# Sheet1.net
KiCad netlist of a schematic drawn in Altium Designer
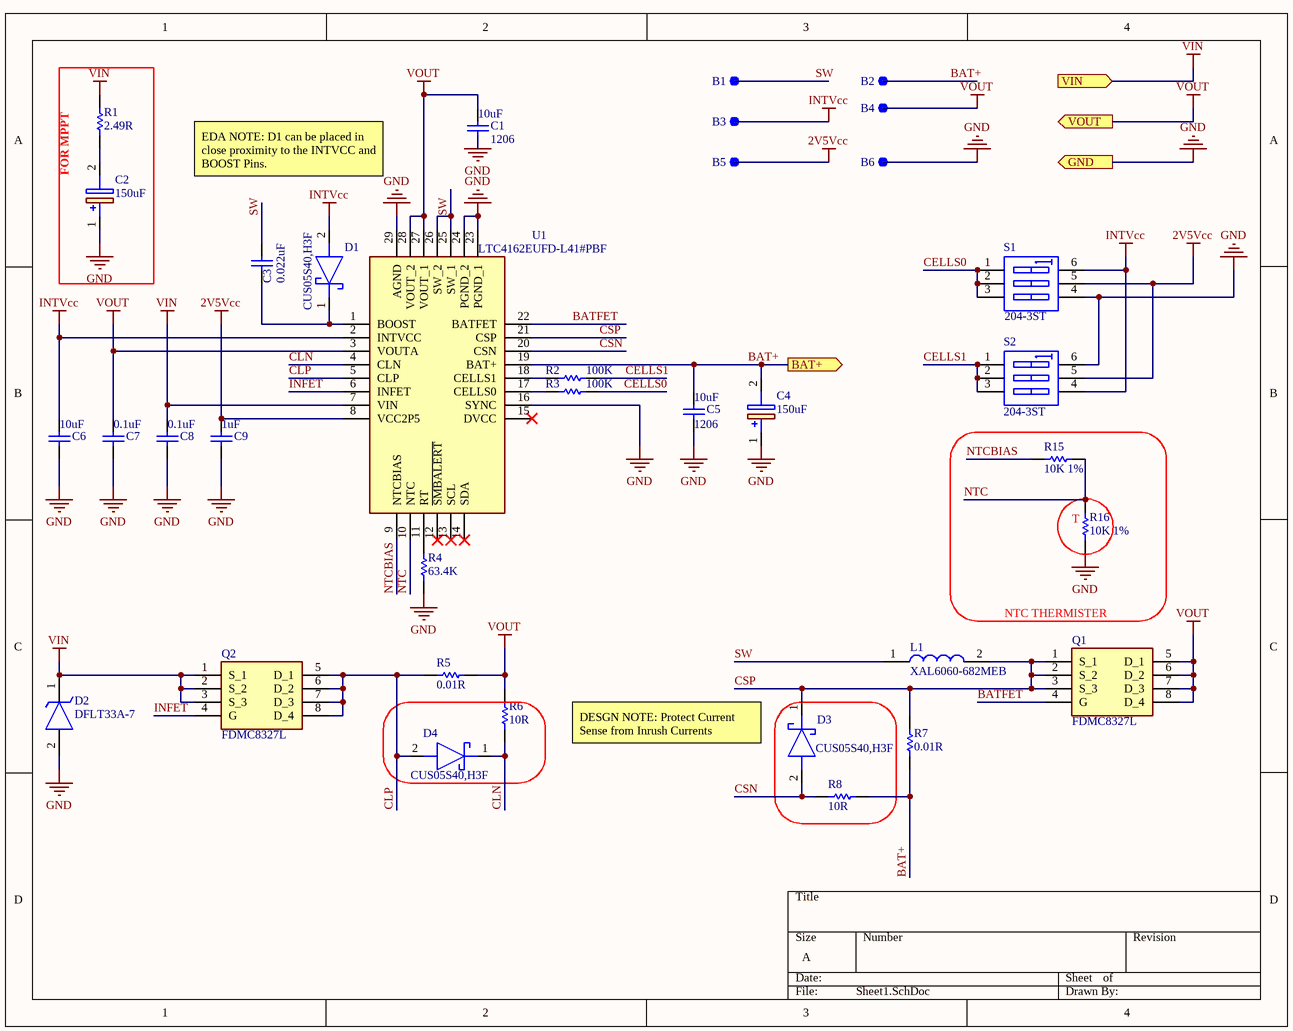
[diagram p0: Sheet1.SchDoc]

(export (version "E")
  (design (tool "Eeschema 10.0.6"))
  (components
    (comp (ref "B1")
      (value "~")
      (footprint "Pads:TPS127")
      (description "Through Hole Pad")
      (libsource (lib "Pads") (part "Single SMD Pad (Round)"))
    )
    (comp (ref "B2")
      (value "~")
      (footprint "Pads:TPS127")
      (description "Through Hole Pad")
      (libsource (lib "Pads") (part "Single SMD Pad (Round)"))
    )
    (comp (ref "B3")
      (value "~")
      (footprint "Pads:TPS127")
      (description "Through Hole Pad")
      (libsource (lib "Pads") (part "Single SMD Pad (Round)"))
    )
    (comp (ref "B4")
      (value "~")
      (footprint "Pads:TPS127")
      (description "Through Hole Pad")
      (libsource (lib "Pads") (part "Single SMD Pad (Round)"))
    )
    (comp (ref "B5")
      (value "~")
      (footprint "Pads:TPS127")
      (description "Through Hole Pad")
      (libsource (lib "Pads") (part "Single SMD Pad (Round)"))
    )
    (comp (ref "B6")
      (value "~")
      (footprint "Pads:TPS127")
      (description "Through Hole Pad")
      (libsource (lib "Pads") (part "Single SMD Pad (Round)"))
    )
    (comp (ref "C1")
      (value "1206")
      (footprint "CAPC3216X152N")
      (description "Capacitor")
      (fields (field (name "ALTIUM_VALUE") "10uF") (field (name "PUBLISHER") "Altium Limited"))
      (libsource (lib "Miscellaneous Devices") (part "Cap"))
    )
    (comp (ref "C2")
      (value "150uF")
      (footprint "SamacSys:CAPAE1030X1050N")
      (description "Capacitor Polarised")
      (fields (field (name "MANUFACTURER_PART_NUMBER") "EEEFK1H151P"))
      (libsource (lib "*") (part "EEEFK1H151P"))
    )
    (comp (ref "C3")
      (value "0.022uF")
      (footprint "Capacitors SMD:CAPC1608X80N")
      (description "Capacitor")
      (fields (field (name "Comment") "Cap") (field (name "PUBLISHER") "Altium Limited"))
      (libsource (lib "Miscellaneous Devices") (part "Cap"))
    )
    (comp (ref "C4")
      (value "150uF")
      (footprint "SamacSys:CAPAE1030X1050N")
      (description "Capacitor Polarised")
      (fields (field (name "MANUFACTURER_PART_NUMBER") "EEEFK1H151P"))
      (libsource (lib "*") (part "EEEFK1H151P"))
    )
    (comp (ref "C5")
      (value "1206")
      (footprint "CAPC3216X152N")
      (description "Capacitor")
      (fields (field (name "ALTIUM_VALUE") "10uF") (field (name "PUBLISHER") "Altium Limited"))
      (libsource (lib "Miscellaneous Devices") (part "Cap"))
    )
    (comp (ref "C6")
      (value "10uF")
      (footprint "Capacitors SMD:CAPC1608X80N")
      (description "Capacitor")
      (fields (field (name "Comment") "Cap") (field (name "PUBLISHER") "Altium Limited"))
      (libsource (lib "Miscellaneous Devices") (part "Cap"))
    )
    (comp (ref "C7")
      (value "0.1uF")
      (footprint "Capacitors SMD:CAPC1608X80N")
      (description "Capacitor")
      (fields (field (name "Comment") "Cap") (field (name "PUBLISHER") "Altium Limited"))
      (libsource (lib "Miscellaneous Devices") (part "Cap"))
    )
    (comp (ref "C8")
      (value "0.1uF")
      (footprint "Capacitors SMD:CAPC1608X80N")
      (description "Capacitor")
      (fields (field (name "Comment") "Cap") (field (name "PUBLISHER") "Altium Limited"))
      (libsource (lib "Miscellaneous Devices") (part "Cap"))
    )
    (comp (ref "C9")
      (value "1uF")
      (footprint "Capacitors SMD:CAPC1608X80N")
      (description "Capacitor")
      (fields (field (name "Comment") "Cap") (field (name "PUBLISHER") "Altium Limited"))
      (libsource (lib "Miscellaneous Devices") (part "Cap"))
    )
    (comp (ref "D1")
      (value "CUS05S40,H3F")
      (footprint "SamacSys:1SS357TPH3F")
      (description "Schottky Diode")
      (fields (field (name "MOUSER PART NUMBER") "757-CUS05S40H3F"))
      (libsource (lib "*") (part "CUS05S40,H3F"))
    )
    (comp (ref "D2")
      (value "DFLT33A-7")
      (footprint "SamacSys:POWERDI123_1")
      (description "TVS Diode (Uni-directional)")
      (fields
        (field (name "MANUFACTURER_PART_NUMBER") "DFLT27A-7")
        (field (name "MOUSER PART NUMBER") "621-DFLT27A-7")
      )
      (libsource (lib "*") (part "DFLT27A-7"))
    )
    (comp (ref "D3")
      (value "CUS05S40,H3F")
      (footprint "SamacSys:1SS357TPH3F")
      (description "Schottky Diode")
      (fields (field (name "MOUSER PART NUMBER") "757-CUS05S40H3F"))
      (libsource (lib "*") (part "CUS05S40,H3F"))
    )
    (comp (ref "D4")
      (value "CUS05S40,H3F")
      (footprint "SamacSys:1SS357TPH3F")
      (description "Schottky Diode")
      (fields (field (name "MOUSER PART NUMBER") "757-CUS05S40H3F"))
      (libsource (lib "*") (part "CUS05S40,H3F"))
    )
    (comp (ref "L1")
      (value "XAL6060-682MEB")
      (footprint "SamacSys:XAL6060822MEB")
      (description "Inductor")
      (fields (field (name "MOUSER PART NUMBER") "994-XAL6060-682MEB"))
      (libsource (lib "*") (part "XAL6060-682MEB"))
    )
    (comp (ref "Q1")
      (value "FDMC8327L")
      (footprint "SamacSys:FDMC86139P")
      (description "MOSFET (N-Channel)")
      (fields (field (name "MOUSER PART NUMBER") "512-FDMC8327L"))
      (libsource (lib "*") (part "FDMC8327L"))
    )
    (comp (ref "Q2")
      (value "FDMC8327L")
      (footprint "SamacSys:FDMC86139P")
      (description "MOSFET (N-Channel)")
      (fields (field (name "MOUSER PART NUMBER") "512-FDMC8327L"))
      (libsource (lib "*") (part "FDMC8327L"))
    )
    (comp (ref "R1")
      (value "2.49R")
      (footprint "Resistors SMD:RESC3216X60N")
      (description "Semiconductor Resistor")
      (fields (field (name "Comment") "Res Semi") (field (name "PUBLISHER") "Altium Limited"))
      (libsource (lib "Miscellaneous Devices") (part "Res Semi"))
    )
    (comp (ref "R2")
      (value "100K")
      (footprint "RESC1608X55N")
      (description "Semiconductor Resistor")
      (fields (field (name "Comment") "Res Semi") (field (name "PUBLISHER") "Altium Limited"))
      (libsource (lib "Miscellaneous Devices") (part "Res Semi"))
    )
    (comp (ref "R3")
      (value "100K")
      (footprint "RESC1608X55N")
      (description "Semiconductor Resistor")
      (fields (field (name "Comment") "Res Semi") (field (name "PUBLISHER") "Altium Limited"))
      (libsource (lib "Miscellaneous Devices") (part "Res Semi"))
    )
    (comp (ref "R4")
      (value "63.4K")
      (footprint "RESC1608X55N")
      (description "Semiconductor Resistor")
      (fields (field (name "Comment") "Res Semi") (field (name "PUBLISHER") "Altium Limited"))
      (libsource (lib "Miscellaneous Devices") (part "Res Semi"))
    )
    (comp (ref "R5")
      (value "0.01R")
      (footprint "RESC3216X60N")
      (description "Semiconductor Resistor")
      (fields (field (name "Comment") "Res Semi") (field (name "PUBLISHER") "Altium Limited"))
      (libsource (lib "Miscellaneous Devices") (part "Res Semi"))
    )
    (comp (ref "R6")
      (value "10R")
      (footprint "RESC1608X55N")
      (description "Semiconductor Resistor")
      (fields (field (name "Comment") "Res Semi") (field (name "PUBLISHER") "Altium Limited"))
      (libsource (lib "Miscellaneous Devices") (part "Res Semi"))
    )
    (comp (ref "R7")
      (value "0.01R")
      (footprint "RESC3216X60N")
      (description "Semiconductor Resistor")
      (fields (field (name "Comment") "Res Semi") (field (name "PUBLISHER") "Altium Limited"))
      (libsource (lib "Miscellaneous Devices") (part "Res Semi"))
    )
    (comp (ref "R8")
      (value "10R")
      (footprint "RESC1608X55N")
      (description "Semiconductor Resistor")
      (fields (field (name "Comment") "Res Semi") (field (name "PUBLISHER") "Altium Limited"))
      (libsource (lib "Miscellaneous Devices") (part "Res Semi"))
    )
    (comp (ref "R15")
      (value "10K 1%")
      (footprint "RESC1608X55N")
      (description "Semiconductor Resistor")
      (fields (field (name "Comment") "Res Semi") (field (name "PUBLISHER") "Altium Limited"))
      (libsource (lib "Miscellaneous Devices") (part "Res Semi"))
    )
    (comp (ref "R16")
      (value "10K 1%")
      (footprint "RESC1005X40N")
      (description "Semiconductor Resistor")
      (fields (field (name "Comment") "Res Semi") (field (name "PUBLISHER") "Altium Limited"))
      (libsource (lib "Miscellaneous Devices") (part "Res Semi"))
    )
    (comp (ref "S1")
      (value "204-3ST")
      (footprint "204-3ST")
      (description "DIP Switch, 3 Position, SPST")
      (fields (field (name "PUBLISHER") "Altium Limited"))
      (libsource (lib "Miscellaneous Devices") (part "SW DIP-3"))
    )
    (comp (ref "S2")
      (value "204-3ST")
      (footprint "204-3ST")
      (description "DIP Switch, 3 Position, SPST")
      (fields (field (name "PUBLISHER") "Altium Limited"))
      (libsource (lib "Miscellaneous Devices") (part "SW DIP-3"))
    )
    (comp (ref "U1")
      (value "LTC4162EUFD-L41#PBF")
      (footprint "Battery_Charger_LTC4162:LTC4162-L")
      (description "Integrated Circuit")
      (fields (field (name "MOUSER PART NUMBER") "584-4162EUFDL41PB"))
      (libsource (lib "*") (part "LTC4162EUFD-L41#PBF"))
    )
  )
  (nets
    (net (code "1") (name "/BAT+") (class "Default")
      (node (ref "B2") (pin "1") (pinfunction "1_1") (pintype "bidirectional"))
      (node (ref "C4") (pin "2") (pinfunction "-_2") (pintype "passive"))
      (node (ref "C5") (pin "2") (pinfunction "2_2") (pintype "passive"))
      (node (ref "R7") (pin "2") (pinfunction "2_2") (pintype "passive"))
      (node (ref "R8") (pin "1") (pinfunction "1_1") (pintype "passive"))
      (node (ref "U1") (pin "19") (pinfunction "BAT+_19") (pintype "passive"))
    )
    (net (code "2") (name "/BATFET") (class "Default")
      (node (ref "Q1") (pin "4") (pinfunction "G_4") (pintype "passive"))
      (node (ref "U1") (pin "22") (pinfunction "BATFET_22") (pintype "passive"))
    )
    (net (code "3") (name "/CELLS0") (class "Default")
      (node (ref "R3") (pin "2") (pinfunction "2_2") (pintype "passive"))
      (node (ref "S1") (pin "1") (pinfunction "A1_1") (pintype "passive"))
      (node (ref "S1") (pin "2") (pinfunction "A2_2") (pintype "passive"))
      (node (ref "S1") (pin "3") (pinfunction "A3_3") (pintype "passive"))
    )
    (net (code "4") (name "/CELLS1") (class "Default")
      (node (ref "R2") (pin "2") (pinfunction "2_2") (pintype "passive"))
      (node (ref "S2") (pin "1") (pinfunction "A1_1") (pintype "passive"))
      (node (ref "S2") (pin "2") (pinfunction "A2_2") (pintype "passive"))
      (node (ref "S2") (pin "3") (pinfunction "A3_3") (pintype "passive"))
    )
    (net (code "5") (name "/CLN") (class "Default")
      (node (ref "D4") (pin "1") (pinfunction "K_1") (pintype "passive"))
      (node (ref "R6") (pin "1") (pinfunction "1_1") (pintype "passive"))
      (node (ref "U1") (pin "4") (pinfunction "CLN_4") (pintype "passive"))
    )
    (net (code "6") (name "/CLP") (class "Default")
      (node (ref "D4") (pin "2") (pinfunction "A_2") (pintype "passive"))
      (node (ref "Q2") (pin "5") (pinfunction "D_1_5") (pintype "passive"))
      (node (ref "Q2") (pin "6") (pinfunction "D_2_6") (pintype "passive"))
      (node (ref "Q2") (pin "7") (pinfunction "D_3_7") (pintype "passive"))
      (node (ref "Q2") (pin "8") (pinfunction "D_4_8") (pintype "passive"))
      (node (ref "R5") (pin "2") (pinfunction "2_2") (pintype "passive"))
      (node (ref "U1") (pin "5") (pinfunction "CLP_5") (pintype "passive"))
    )
    (net (code "7") (name "/CSN") (class "Default")
      (node (ref "D3") (pin "2") (pinfunction "A_2") (pintype "passive"))
      (node (ref "R8") (pin "2") (pinfunction "2_2") (pintype "passive"))
      (node (ref "U1") (pin "20") (pinfunction "CSN_20") (pintype "passive"))
    )
    (net (code "8") (name "/CSP") (class "Default")
      (node (ref "D3") (pin "1") (pinfunction "K_1") (pintype "passive"))
      (node (ref "L1") (pin "2") (pinfunction "2_2") (pintype "passive"))
      (node (ref "Q1") (pin "1") (pinfunction "S_1_1") (pintype "passive"))
      (node (ref "Q1") (pin "2") (pinfunction "S_2_2") (pintype "passive"))
      (node (ref "Q1") (pin "3") (pinfunction "S_3_3") (pintype "passive"))
      (node (ref "R7") (pin "1") (pinfunction "1_1") (pintype "passive"))
      (node (ref "U1") (pin "21") (pinfunction "CSP_21") (pintype "passive"))
    )
    (net (code "9") (name "/INFET") (class "Default")
      (node (ref "Q2") (pin "4") (pinfunction "G_4") (pintype "passive"))
      (node (ref "U1") (pin "6") (pinfunction "INFET_6") (pintype "passive"))
    )
    (net (code "10") (name "/NTC") (class "Default")
      (node (ref "R15") (pin "1") (pinfunction "1_1") (pintype "passive"))
      (node (ref "R16") (pin "1") (pinfunction "1_1") (pintype "passive"))
      (node (ref "U1") (pin "10") (pinfunction "NTC_10") (pintype "passive"))
    )
    (net (code "11") (name "/NTCBIAS") (class "Default")
      (node (ref "R15") (pin "2") (pinfunction "2_2") (pintype "passive"))
      (node (ref "U1") (pin "9") (pinfunction "NTCBIAS_9") (pintype "passive"))
    )
    (net (code "12") (name "/SW") (class "Default")
      (node (ref "B1") (pin "1") (pinfunction "1_1") (pintype "bidirectional"))
      (node (ref "C3") (pin "1") (pinfunction "1_1") (pintype "passive"))
      (node (ref "L1") (pin "1") (pinfunction "1_1") (pintype "passive"))
      (node (ref "U1") (pin "25") (pinfunction "SW_1_25") (pintype "passive"))
      (node (ref "U1") (pin "26") (pinfunction "SW_2_26") (pintype "passive"))
    )
    (net (code "13") (name "2V5Vcc") (class "Default")
      (node (ref "B5") (pin "1") (pinfunction "1_1") (pintype "bidirectional"))
      (node (ref "C9") (pin "2") (pinfunction "2_2") (pintype "passive"))
      (node (ref "S1") (pin "5") (pinfunction "B2_5") (pintype "passive"))
      (node (ref "S2") (pin "5") (pinfunction "B2_5") (pintype "passive"))
      (node (ref "U1") (pin "8") (pinfunction "VCC2P5_8") (pintype "passive"))
    )
    (net (code "14") (name "GND") (class "Default")
      (node (ref "B6") (pin "1") (pinfunction "1_1") (pintype "bidirectional"))
      (node (ref "C1") (pin "1") (pinfunction "1_1") (pintype "passive"))
      (node (ref "C2") (pin "1") (pinfunction "+_1") (pintype "passive"))
      (node (ref "C4") (pin "1") (pinfunction "+_1") (pintype "passive"))
      (node (ref "C5") (pin "1") (pinfunction "1_1") (pintype "passive"))
      (node (ref "C6") (pin "1") (pinfunction "1_1") (pintype "passive"))
      (node (ref "C7") (pin "1") (pinfunction "1_1") (pintype "passive"))
      (node (ref "C8") (pin "1") (pinfunction "1_1") (pintype "passive"))
      (node (ref "C9") (pin "1") (pinfunction "1_1") (pintype "passive"))
      (node (ref "D2") (pin "2") (pinfunction "A_2") (pintype "passive"))
      (node (ref "R16") (pin "2") (pinfunction "2_2") (pintype "passive"))
      (node (ref "R4") (pin "1") (pinfunction "1_1") (pintype "passive"))
      (node (ref "S1") (pin "4") (pinfunction "B3_4") (pintype "passive"))
      (node (ref "S2") (pin "6") (pinfunction "B1_6") (pintype "passive"))
      (node (ref "U1") (pin "16") (pinfunction "SYNC_16") (pintype "passive"))
      (node (ref "U1") (pin "23") (pinfunction "PGND_1_23") (pintype "passive"))
      (node (ref "U1") (pin "24") (pinfunction "PGND_2_24") (pintype "passive"))
      (node (ref "U1") (pin "29") (pinfunction "AGND_29") (pintype "passive"))
    )
    (net (code "15") (name "INTVcc") (class "Default")
      (node (ref "B3") (pin "1") (pinfunction "1_1") (pintype "bidirectional"))
      (node (ref "C6") (pin "2") (pinfunction "2_2") (pintype "passive"))
      (node (ref "D1") (pin "2") (pinfunction "A_2") (pintype "passive"))
      (node (ref "S1") (pin "6") (pinfunction "B1_6") (pintype "passive"))
      (node (ref "S2") (pin "4") (pinfunction "B3_4") (pintype "passive"))
      (node (ref "U1") (pin "2") (pinfunction "INTVCC_2") (pintype "passive"))
    )
    (net (code "16") (name "Net-(C2--)") (class "Default")
      (node (ref "C2") (pin "2") (pinfunction "-_2") (pintype "passive"))
      (node (ref "R1") (pin "1") (pinfunction "1_1") (pintype "passive"))
    )
    (net (code "17") (name "Net-(D1-K)") (class "Default")
      (node (ref "C3") (pin "2") (pinfunction "2_2") (pintype "passive"))
      (node (ref "D1") (pin "1") (pinfunction "K_1") (pintype "passive"))
      (node (ref "U1") (pin "1") (pinfunction "BOOST_1") (pintype "passive"))
    )
    (net (code "18") (name "Net-(U1-CELLS0)") (class "Default")
      (node (ref "R3") (pin "1") (pinfunction "1_1") (pintype "passive"))
      (node (ref "U1") (pin "17") (pinfunction "CELLS0_17") (pintype "passive"))
    )
    (net (code "19") (name "Net-(U1-CELLS1)") (class "Default")
      (node (ref "R2") (pin "1") (pinfunction "1_1") (pintype "passive"))
      (node (ref "U1") (pin "18") (pinfunction "CELLS1_18") (pintype "passive"))
    )
    (net (code "20") (name "Net-(U1-RT)") (class "Default")
      (node (ref "R4") (pin "2") (pinfunction "2_2") (pintype "passive"))
      (node (ref "U1") (pin "11") (pinfunction "RT_11") (pintype "passive"))
    )
    (net (code "21") (name "VIN") (class "Default")
      (node (ref "C8") (pin "2") (pinfunction "2_2") (pintype "passive"))
      (node (ref "D2") (pin "1") (pinfunction "K_1") (pintype "passive"))
      (node (ref "Q2") (pin "1") (pinfunction "S_1_1") (pintype "passive"))
      (node (ref "Q2") (pin "2") (pinfunction "S_2_2") (pintype "passive"))
      (node (ref "Q2") (pin "3") (pinfunction "S_3_3") (pintype "passive"))
      (node (ref "R1") (pin "2") (pinfunction "2_2") (pintype "passive"))
      (node (ref "U1") (pin "7") (pinfunction "VIN_7") (pintype "passive"))
    )
    (net (code "22") (name "VOUT") (class "Default")
      (node (ref "B4") (pin "1") (pinfunction "1_1") (pintype "bidirectional"))
      (node (ref "C1") (pin "2") (pinfunction "2_2") (pintype "passive"))
      (node (ref "C7") (pin "2") (pinfunction "2_2") (pintype "passive"))
      (node (ref "Q1") (pin "5") (pinfunction "D_1_5") (pintype "passive"))
      (node (ref "Q1") (pin "6") (pinfunction "D_2_6") (pintype "passive"))
      (node (ref "Q1") (pin "7") (pinfunction "D_3_7") (pintype "passive"))
      (node (ref "Q1") (pin "8") (pinfunction "D_4_8") (pintype "passive"))
      (node (ref "R5") (pin "1") (pinfunction "1_1") (pintype "passive"))
      (node (ref "R6") (pin "2") (pinfunction "2_2") (pintype "passive"))
      (node (ref "U1") (pin "27") (pinfunction "VOUT_1_27") (pintype "passive"))
      (node (ref "U1") (pin "28") (pinfunction "VOUT_2_28") (pintype "passive"))
      (node (ref "U1") (pin "3") (pinfunction "VOUTA_3") (pintype "passive"))
    )
    (net (code "23") (name "unconnected-(U1-DVCC-Pad15)") (class "Default")
      (node (ref "U1") (pin "15") (pinfunction "DVCC_15") (pintype "passive+no_connect"))
    )
    (net (code "24") (name "unconnected-(U1-SCL-Pad13)") (class "Default")
      (node (ref "U1") (pin "13") (pinfunction "SCL_13") (pintype "passive+no_connect"))
    )
    (net (code "25") (name "unconnected-(U1-SDA-Pad14)") (class "Default")
      (node (ref "U1") (pin "14") (pinfunction "SDA_14") (pintype "passive+no_connect"))
    )
    (net (code "26") (name "unconnected-(U1-~{SMBALERT}-Pad12)") (class "Default")
      (node (ref "U1") (pin "12") (pinfunction "~{SMBALERT}_12") (pintype "passive+no_connect"))
    )
  )
)
